# pmc2_1.net
KiCad netlist of a schematic drawn in EAGLE
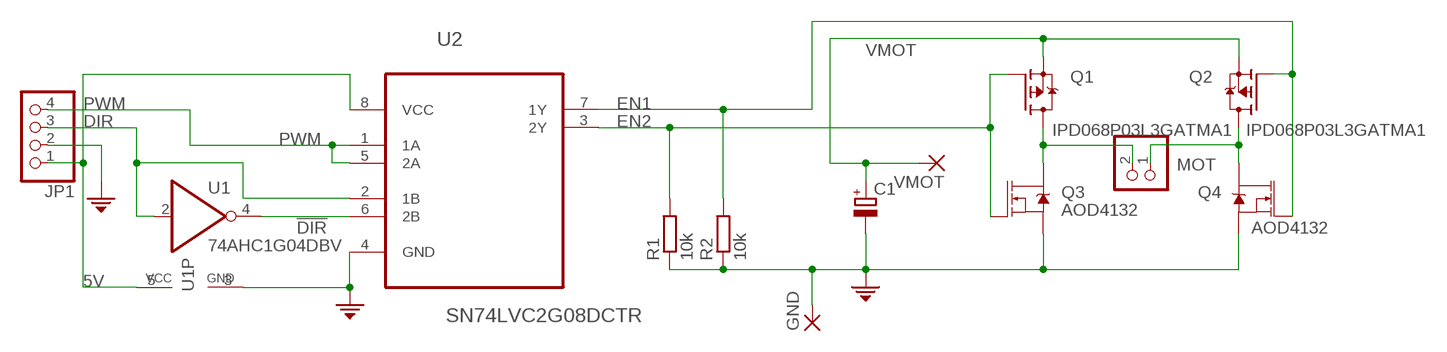
[diagram p0: schematic, sheet 1]

(export (version "E")
  (design (tool "Eeschema 10.0.6"))
  (components
    (comp (ref "C1")
      (value "CPOL-EUE5-13")
      (footprint "eagle-import:E5-13")
      (libsource (lib "eagle-import") (part "CPOL-EUE5-13"))
    )
    (comp (ref "GND")
      (value "SMD5")
      (footprint "eagle-import:SMD2,54-5,08")
      (libsource (lib "eagle-import") (part "SMD5"))
    )
    (comp (ref "JP1")
      (value "PINHD-1X4/90")
      (footprint "eagle-import:1X04_90")
      (libsource (lib "eagle-import") (part "PINHD-1X4/90"))
    )
    (comp (ref "MOT")
      (value "PINHD-1X2")
      (footprint "eagle-import:1X02")
      (libsource (lib "eagle-import") (part "PINHD-1X2"))
    )
    (comp (ref "Q1")
      (value "IPD068P03L3GATMA1")
      (footprint "eagle-import:TO252")
      (libsource (lib "eagle-import") (part "FDD4141TO252"))
    )
    (comp (ref "Q2")
      (value "IPD068P03L3GATMA1")
      (footprint "eagle-import:TO252")
      (libsource (lib "eagle-import") (part "FDD4141TO252"))
    )
    (comp (ref "Q3")
      (value "AOD4132")
      (footprint "eagle-import:DPAK")
      (libsource (lib "eagle-import") (part "MOSFET-NCH-FDD8780"))
    )
    (comp (ref "Q4")
      (value "AOD4132")
      (footprint "eagle-import:DPAK")
      (libsource (lib "eagle-import") (part "MOSFET-NCH-FDD8780"))
    )
    (comp (ref "R1")
      (value "10k")
      (footprint "eagle-import:R0603")
      (libsource (lib "eagle-import") (part "R-EU_R0603"))
    )
    (comp (ref "R2")
      (value "10k")
      (footprint "eagle-import:R0603")
      (libsource (lib "eagle-import") (part "R-EU_R0603"))
    )
    (comp (ref "U1")
      (value "74AHC1G04DBV")
      (footprint "eagle-import:SOT23-5")
      (libsource (lib "eagle-import") (part "741G04DBVAHC"))
    )
    (comp (ref "U2")
      (value "SN74LVC2G08DCTR")
      (footprint "eagle-import:SOP65P400X130-8N")
      (libsource (lib "eagle-import") (part "SN74LVC2G08DCTR"))
    )
    (comp (ref "VMOT")
      (value "SMD5")
      (footprint "eagle-import:SMD2,54-5,08")
      (libsource (lib "eagle-import") (part "SMD5"))
    )
  )
  (nets
    (net (code "1") (name "/5V") (class "Default")
      (node (ref "JP1") (pin "1") (pinfunction "1_1") (pintype "passive"))
      (node (ref "U1") (pin "5") (pinfunction "VCC_5") (pintype "power_in"))
      (node (ref "U2") (pin "8") (pinfunction "VCC_8") (pintype "power_in"))
    )
    (net (code "2") (name "/DIR") (class "Default")
      (node (ref "JP1") (pin "3") (pinfunction "3_3") (pintype "passive"))
      (node (ref "U1") (pin "2") (pinfunction "I_2") (pintype "input"))
      (node (ref "U2") (pin "2") (pinfunction "1B_2") (pintype "input"))
    )
    (net (code "3") (name "/EN1") (class "Default")
      (node (ref "Q2") (pin "1") (pinfunction "G_1") (pintype "passive"))
      (node (ref "Q4") (pin "1") (pinfunction "G_1") (pintype "bidirectional"))
      (node (ref "R2") (pin "2") (pinfunction "2_2") (pintype "passive"))
      (node (ref "U2") (pin "7") (pinfunction "1Y_7") (pintype "output"))
    )
    (net (code "4") (name "/EN2") (class "Default")
      (node (ref "Q1") (pin "1") (pinfunction "G_1") (pintype "passive"))
      (node (ref "Q3") (pin "1") (pinfunction "G_1") (pintype "bidirectional"))
      (node (ref "R1") (pin "2") (pinfunction "2_2") (pintype "passive"))
      (node (ref "U2") (pin "3") (pinfunction "2Y_3") (pintype "output"))
    )
    (net (code "5") (name "/PWM") (class "Default")
      (node (ref "JP1") (pin "4") (pinfunction "4_4") (pintype "passive"))
      (node (ref "U2") (pin "1") (pinfunction "1A_1") (pintype "input"))
      (node (ref "U2") (pin "5") (pinfunction "2A_5") (pintype "input"))
    )
    (net (code "6") (name "/VMOT") (class "Default")
      (node (ref "C1") (pin "+") (pinfunction "+_+") (pintype "passive"))
      (node (ref "Q1") (pin "2") (pinfunction "S_2") (pintype "passive"))
      (node (ref "Q2") (pin "2") (pinfunction "S_2") (pintype "passive"))
      (node (ref "VMOT") (pin "1") (pinfunction "P_1") (pintype "passive"))
    )
    (net (code "7") (name "/~{DIR}") (class "Default")
      (node (ref "U1") (pin "4") (pinfunction "O_4") (pintype "output"))
      (node (ref "U2") (pin "6") (pinfunction "2B_6") (pintype "input"))
    )
    (net (code "8") (name "GND") (class "Default")
      (node (ref "C1") (pin "-") (pinfunction "-_-") (pintype "passive"))
      (node (ref "GND") (pin "1") (pinfunction "P_1") (pintype "passive"))
      (node (ref "JP1") (pin "2") (pinfunction "2_2") (pintype "passive"))
      (node (ref "Q3") (pin "3") (pinfunction "S_3") (pintype "bidirectional"))
      (node (ref "Q4") (pin "3") (pinfunction "S_3") (pintype "bidirectional"))
      (node (ref "R1") (pin "1") (pinfunction "1_1") (pintype "passive"))
      (node (ref "R2") (pin "1") (pinfunction "1_1") (pintype "passive"))
      (node (ref "U1") (pin "3") (pinfunction "GND_3") (pintype "power_in"))
      (node (ref "U2") (pin "4") (pinfunction "GND_4") (pintype "passive"))
    )
    (net (code "9") (name "Net-(Q1-D)") (class "Default")
      (node (ref "MOT") (pin "2") (pinfunction "2_2") (pintype "passive"))
      (node (ref "Q1") (pin "3") (pinfunction "D_3") (pintype "passive"))
      (node (ref "Q3") (pin "4") (pinfunction "D_4") (pintype "bidirectional"))
    )
    (net (code "10") (name "Net-(Q2-D)") (class "Default")
      (node (ref "MOT") (pin "1") (pinfunction "1_1") (pintype "passive"))
      (node (ref "Q2") (pin "3") (pinfunction "D_3") (pintype "passive"))
      (node (ref "Q4") (pin "4") (pinfunction "D_4") (pintype "bidirectional"))
    )
  )
)
